# SCH_Snoopy-LED-Circuit_2025-12-06.net
KiCad netlist of a schematic drawn in EasyEDA
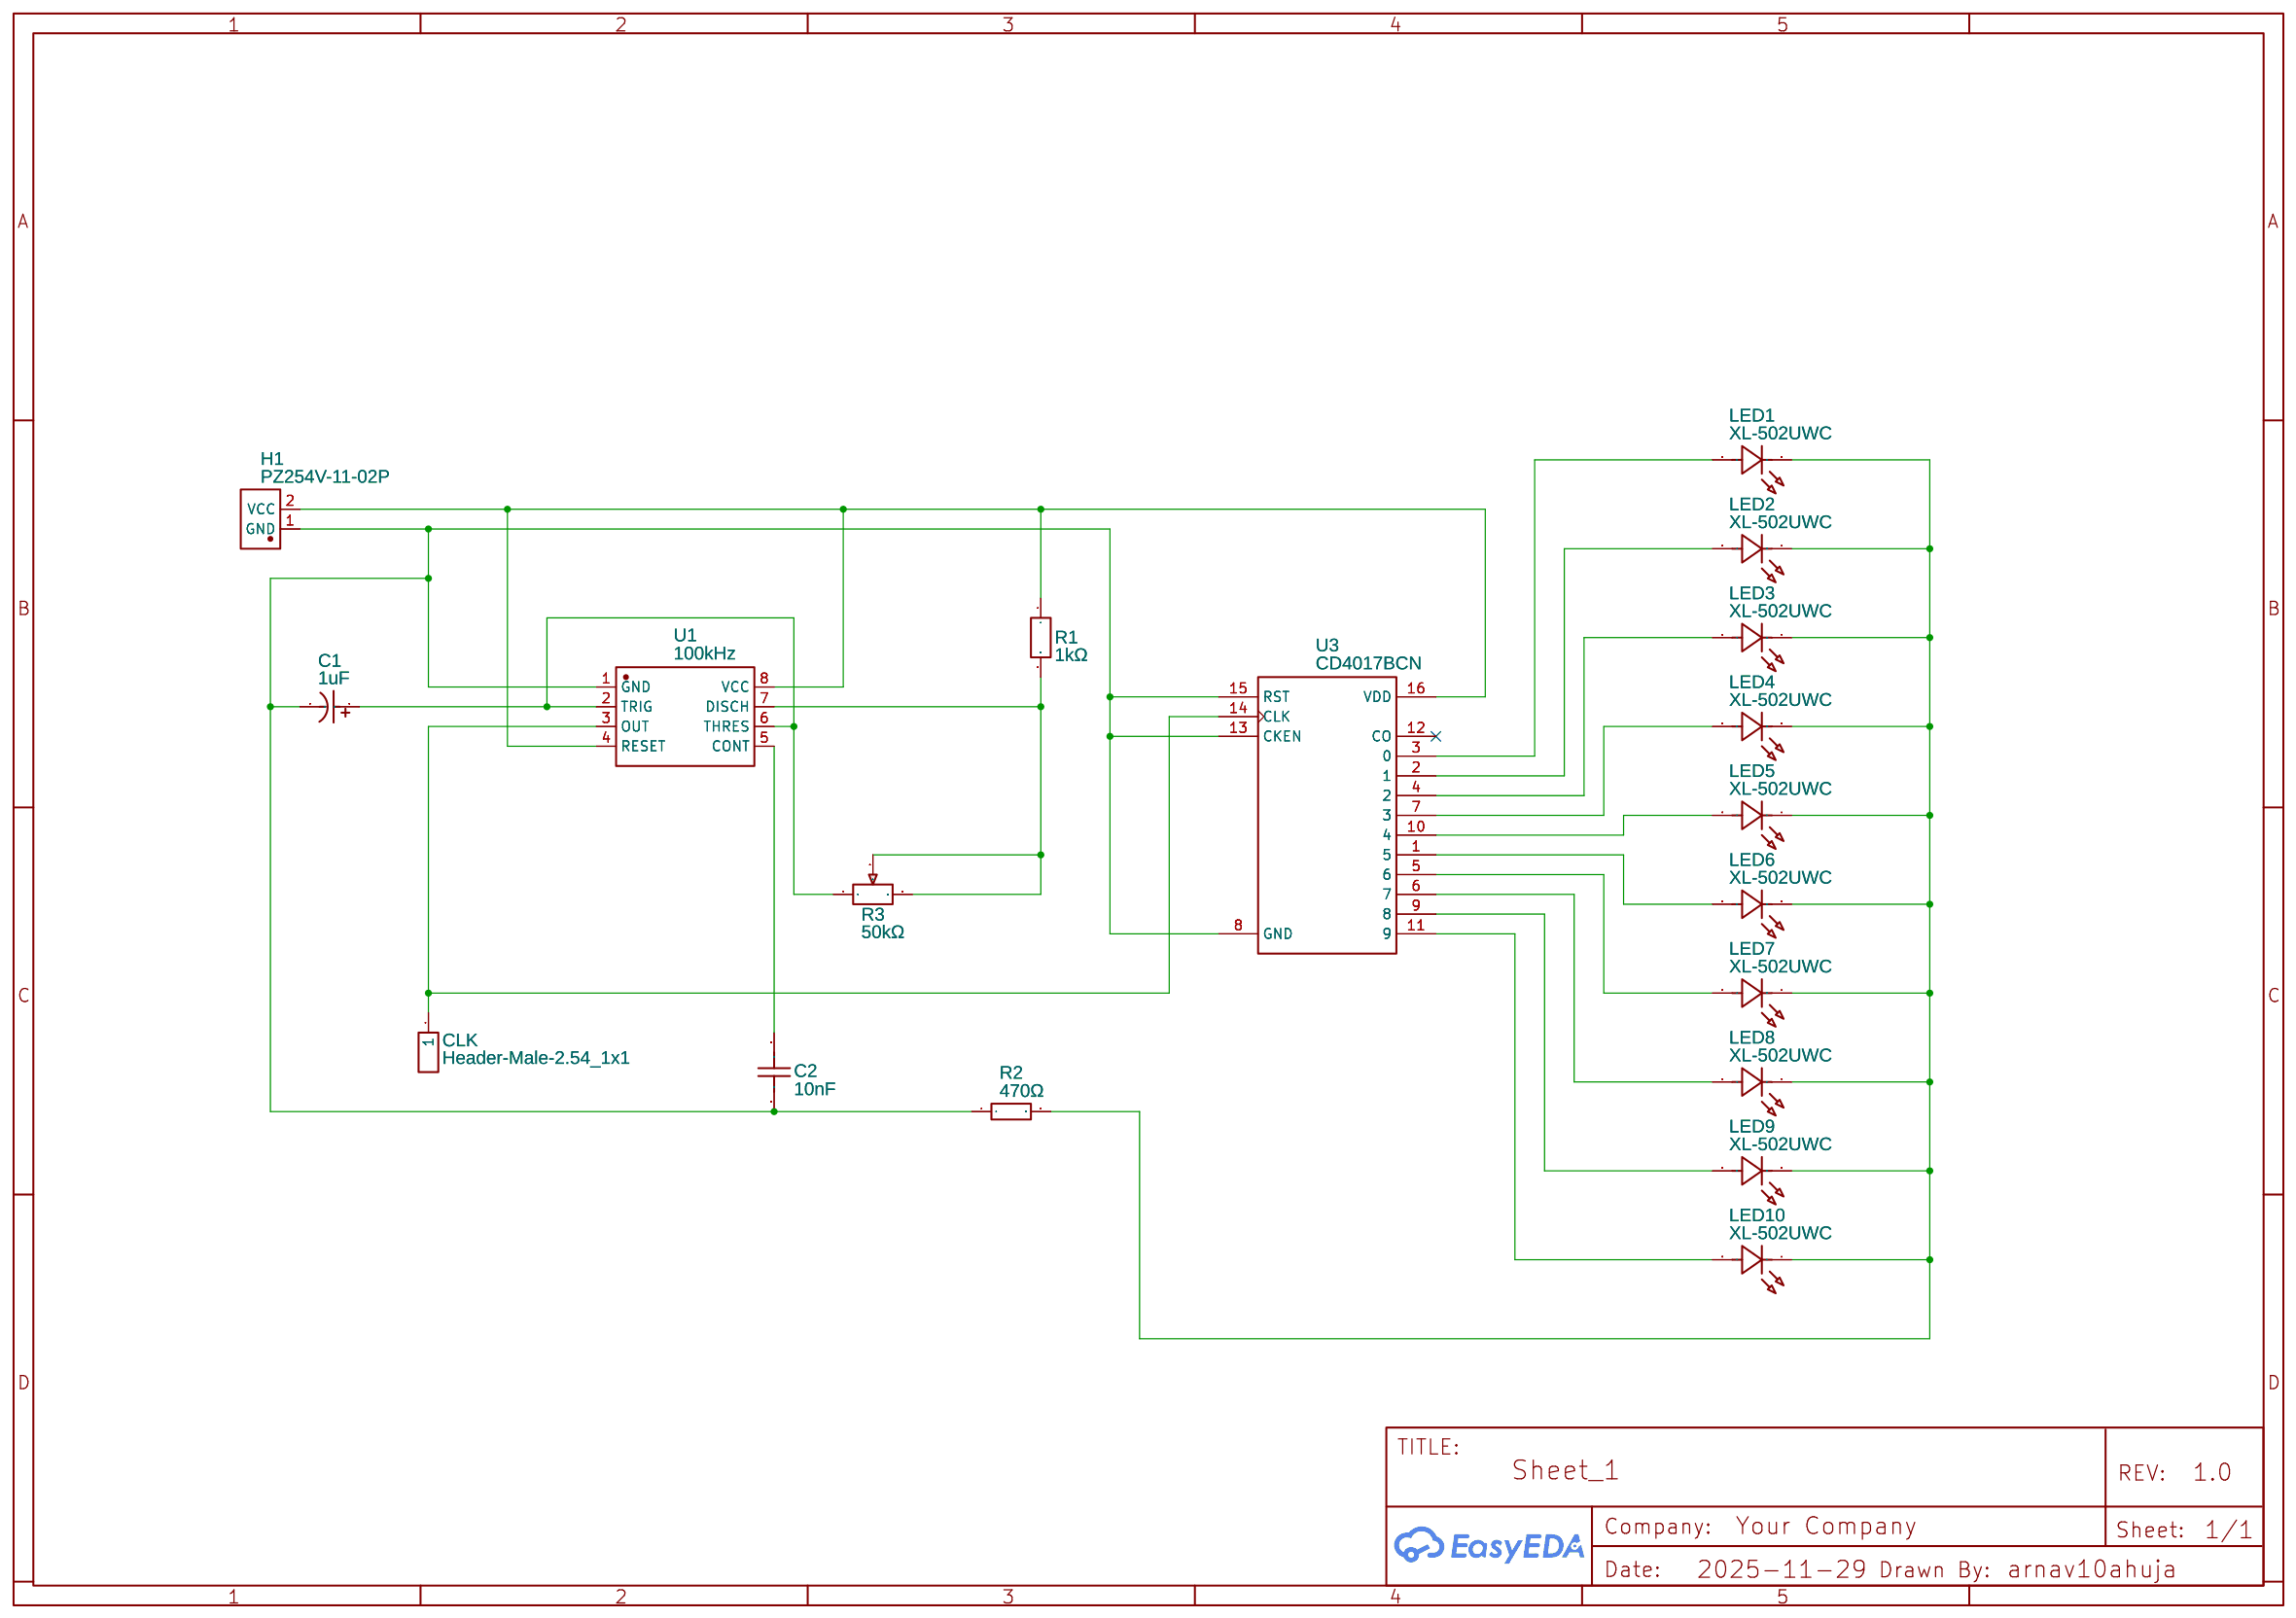
[diagram p0: schematic sheet]

(export (version "E")
  (design (tool "Eeschema 10.0.6"))
  (components
    (comp (ref "C1")
      (value "1uF")
      (fields (field (name "Manufacturer Part") "KF010M050C110A") (field (name "Manufacturer") "CapXon(丰宾)"))
      (libsource (lib "") (part "KF010M050C110A"))
    )
    (comp (ref "C2")
      (value "10nF")
      (fields (field (name "Manufacturer Part") "N09F1B103MN0B0S0N0") (field (name "Manufacturer") "STE(松田)"))
      (libsource (lib "") (part "N09F1B103MN0B0S0N0"))
    )
    (comp (ref "CLK")
      (value "Header-Male-2.54_1x1")
      (fields (field (name "Manufacturer Part") "2.54-1*1P针") (field (name "Manufacturer") "BOOMELE(博穆精密)"))
      (libsource (lib "") (part "Header-Male-2.54_1x1"))
    )
    (comp (ref "H1")
      (value "PZ254V-11-02P")
      (fields (field (name "Manufacturer") "XFCN(兴飞)"))
      (libsource (lib "") (part "PZ254V-11-02P"))
    )
    (comp (ref "LED1")
      (value "XL-502UWC")
      (fields (field (name "Manufacturer") "XINGLIGHT(成兴光)"))
      (libsource (lib "") (part "XL-502UWC"))
    )
    (comp (ref "LED2")
      (value "XL-502UWC")
      (fields (field (name "Manufacturer") "XINGLIGHT(成兴光)"))
      (libsource (lib "") (part "XL-502UWC"))
    )
    (comp (ref "LED3")
      (value "XL-502UWC")
      (fields (field (name "Manufacturer") "XINGLIGHT(成兴光)"))
      (libsource (lib "") (part "XL-502UWC"))
    )
    (comp (ref "LED4")
      (value "XL-502UWC")
      (fields (field (name "Manufacturer") "XINGLIGHT(成兴光)"))
      (libsource (lib "") (part "XL-502UWC"))
    )
    (comp (ref "LED5")
      (value "XL-502UWC")
      (fields (field (name "Manufacturer") "XINGLIGHT(成兴光)"))
      (libsource (lib "") (part "XL-502UWC"))
    )
    (comp (ref "LED6")
      (value "XL-502UWC")
      (fields (field (name "Manufacturer") "XINGLIGHT(成兴光)"))
      (libsource (lib "") (part "XL-502UWC"))
    )
    (comp (ref "LED7")
      (value "XL-502UWC")
      (fields (field (name "Manufacturer") "XINGLIGHT(成兴光)"))
      (libsource (lib "") (part "XL-502UWC"))
    )
    (comp (ref "LED8")
      (value "XL-502UWC")
      (fields (field (name "Manufacturer") "XINGLIGHT(成兴光)"))
      (libsource (lib "") (part "XL-502UWC"))
    )
    (comp (ref "LED9")
      (value "XL-502UWC")
      (fields (field (name "Manufacturer") "XINGLIGHT(成兴光)"))
      (libsource (lib "") (part "XL-502UWC"))
    )
    (comp (ref "LED10")
      (value "XL-502UWC")
      (fields (field (name "Manufacturer") "XINGLIGHT(成兴光)"))
      (libsource (lib "") (part "XL-502UWC"))
    )
    (comp (ref "R1")
      (value "1kΩ")
      (fields (field (name "Manufacturer Part") "MF1/4W-1KΩ±1%T52") (field (name "Manufacturer") "华星机电"))
      (libsource (lib "") (part "MF1/4W-1KΩ±1%T52"))
    )
    (comp (ref "R2")
      (value "470Ω")
      (fields
        (field (name "Manufacturer Part") "MFR0W4F4700A50")
        (field (name "Manufacturer") "UNI-ROYAL(厚声)")
      )
      (libsource (lib "") (part "MFR0W4F4700A50"))
    )
    (comp (ref "R3")
      (value "50kΩ")
      (fields (field (name "Manufacturer Part") "3296X-1-503") (field (name "Manufacturer") "BOCHEN(博晨)"))
      (libsource (lib "") (part "3296X-1-503_C118912"))
    )
    (comp (ref "U1")
      (value "100kHz")
      (fields (field (name "Manufacturer Part") "NE555P") (field (name "Manufacturer") "TI(德州仪器)"))
      (libsource (lib "") (part "NE555P"))
    )
    (comp (ref "U3") (value "CD4017BCN") (libsource (lib "") (part "CD4017BCN")))
  )
  (nets
    (net (code "1") (name "Net-(H1-GND)") (class "Default")
      (node (ref "C1") (pin "2") (pinfunction "2_2") (pintype "input"))
      (node (ref "C2") (pin "1") (pinfunction "1_1") (pintype "unspecified"))
      (node (ref "H1") (pin "1") (pinfunction "GND_1") (pintype "unspecified"))
      (node (ref "R2") (pin "1") (pinfunction "1_1") (pintype "input"))
      (node (ref "U1") (pin "1") (pinfunction "GND_1") (pintype "unspecified"))
      (node (ref "U3") (pin "13") (pinfunction "CKEN_13") (pintype "unspecified"))
      (node (ref "U3") (pin "15") (pinfunction "RST_15") (pintype "unspecified"))
      (node (ref "U3") (pin "8") (pinfunction "GND_8") (pintype "passive"))
    )
    (net (code "2") (name "Net-(H1-VCC)") (class "Default")
      (node (ref "H1") (pin "2") (pinfunction "VCC_2") (pintype "unspecified"))
      (node (ref "R1") (pin "1") (pinfunction "1_1") (pintype "unspecified"))
      (node (ref "U1") (pin "4") (pinfunction "RESET_4") (pintype "unspecified"))
      (node (ref "U1") (pin "8") (pinfunction "VCC_8") (pintype "unspecified"))
      (node (ref "U3") (pin "16") (pinfunction "VDD_16") (pintype "passive"))
    )
    (net (code "3") (name "Net-(LED1-A)") (class "Default")
      (node (ref "LED1") (pin "2") (pinfunction "A_2") (pintype "unspecified"))
      (node (ref "U3") (pin "3") (pinfunction "0_3") (pintype "output"))
    )
    (net (code "4") (name "Net-(LED1-K)") (class "Default")
      (node (ref "LED1") (pin "1") (pinfunction "K_1") (pintype "unspecified"))
      (node (ref "LED10") (pin "1") (pinfunction "K_1") (pintype "unspecified"))
      (node (ref "LED2") (pin "1") (pinfunction "K_1") (pintype "unspecified"))
      (node (ref "LED3") (pin "1") (pinfunction "K_1") (pintype "unspecified"))
      (node (ref "LED4") (pin "1") (pinfunction "K_1") (pintype "unspecified"))
      (node (ref "LED5") (pin "1") (pinfunction "K_1") (pintype "unspecified"))
      (node (ref "LED6") (pin "1") (pinfunction "K_1") (pintype "unspecified"))
      (node (ref "LED7") (pin "1") (pinfunction "K_1") (pintype "unspecified"))
      (node (ref "LED8") (pin "1") (pinfunction "K_1") (pintype "unspecified"))
      (node (ref "LED9") (pin "1") (pinfunction "K_1") (pintype "unspecified"))
      (node (ref "R2") (pin "2") (pinfunction "2_2") (pintype "input"))
    )
    (net (code "5") (name "Net-(LED2-A)") (class "Default")
      (node (ref "LED2") (pin "2") (pinfunction "A_2") (pintype "unspecified"))
      (node (ref "U3") (pin "2") (pinfunction "1_2") (pintype "output"))
    )
    (net (code "6") (name "Net-(LED3-A)") (class "Default")
      (node (ref "LED3") (pin "2") (pinfunction "A_2") (pintype "unspecified"))
      (node (ref "U3") (pin "4") (pinfunction "2_4") (pintype "output"))
    )
    (net (code "7") (name "Net-(LED4-A)") (class "Default")
      (node (ref "LED4") (pin "2") (pinfunction "A_2") (pintype "unspecified"))
      (node (ref "U3") (pin "7") (pinfunction "3_7") (pintype "output"))
    )
    (net (code "8") (name "Net-(LED5-A)") (class "Default")
      (node (ref "LED5") (pin "2") (pinfunction "A_2") (pintype "unspecified"))
      (node (ref "U3") (pin "10") (pinfunction "4_10") (pintype "output"))
    )
    (net (code "9") (name "Net-(LED6-A)") (class "Default")
      (node (ref "LED6") (pin "2") (pinfunction "A_2") (pintype "unspecified"))
      (node (ref "U3") (pin "1") (pinfunction "5_1") (pintype "output"))
    )
    (net (code "10") (name "Net-(LED7-A)") (class "Default")
      (node (ref "LED7") (pin "2") (pinfunction "A_2") (pintype "unspecified"))
      (node (ref "U3") (pin "5") (pinfunction "6_5") (pintype "output"))
    )
    (net (code "11") (name "Net-(LED8-A)") (class "Default")
      (node (ref "LED8") (pin "2") (pinfunction "A_2") (pintype "unspecified"))
      (node (ref "U3") (pin "6") (pinfunction "7_6") (pintype "output"))
    )
    (net (code "12") (name "Net-(LED9-A)") (class "Default")
      (node (ref "LED9") (pin "2") (pinfunction "A_2") (pintype "unspecified"))
      (node (ref "U3") (pin "9") (pinfunction "8_9") (pintype "output"))
    )
    (net (code "13") (name "Net-(LED10-A)") (class "Default")
      (node (ref "LED10") (pin "2") (pinfunction "A_2") (pintype "unspecified"))
      (node (ref "U3") (pin "11") (pinfunction "9_11") (pintype "output"))
    )
    (net (code "14") (name "Net-(U1-CONT)") (class "Default")
      (node (ref "C2") (pin "2") (pinfunction "2_2") (pintype "unspecified"))
      (node (ref "U1") (pin "5") (pinfunction "CONT_5") (pintype "unspecified"))
    )
    (net (code "15") (name "Net-(U1-DISCH)") (class "Default")
      (node (ref "R1") (pin "2") (pinfunction "2_2") (pintype "unspecified"))
      (node (ref "R3") (pin "2") (pinfunction "2_2") (pintype "input"))
      (node (ref "R3") (pin "3") (pinfunction "3_3") (pintype "input"))
      (node (ref "U1") (pin "7") (pinfunction "DISCH_7") (pintype "unspecified"))
    )
    (net (code "16") (name "Net-(U1-OUT)") (class "Default")
      (node (ref "CLK") (pin "1") (pinfunction "1_1") (pintype "input"))
      (node (ref "U1") (pin "3") (pinfunction "OUT_3") (pintype "unspecified"))
      (node (ref "U3") (pin "14") (pinfunction "CLK_14") (pintype "unspecified"))
    )
    (net (code "17") (name "Net-(U1-THRES)") (class "Default")
      (node (ref "C1") (pin "1") (pinfunction "1_1") (pintype "input"))
      (node (ref "R3") (pin "1") (pinfunction "1_1") (pintype "input"))
      (node (ref "U1") (pin "2") (pinfunction "TRIG_2") (pintype "unspecified"))
      (node (ref "U1") (pin "6") (pinfunction "THRES_6") (pintype "unspecified"))
    )
    (net (code "18") (name "unconnected-(U3-CO-Pad12)") (class "Default")
      (node (ref "U3") (pin "12") (pinfunction "CO_12") (pintype "output+no_connect"))
    )
  )
)
